# breakout.net
KiCad netlist of a schematic drawn in Altium Designer
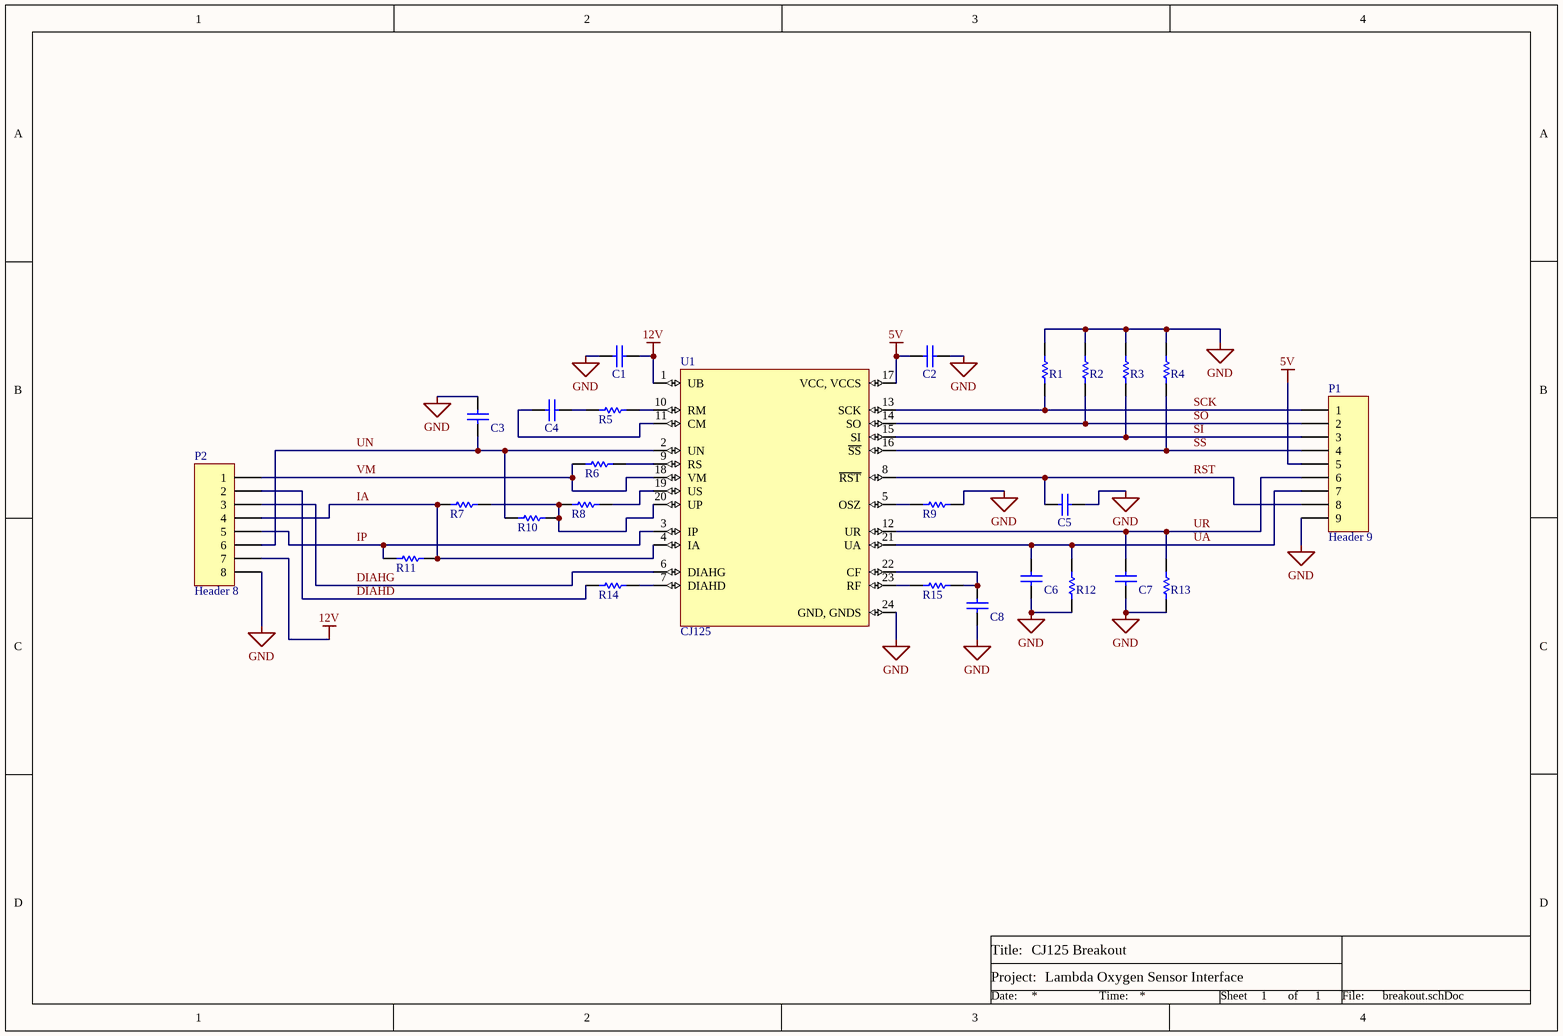
[diagram p0: breakout.schDoc]

(export (version "E")
  (design (tool "Eeschema 10.0.6"))
  (components
    (comp (ref "C1")
      (value "Generic 0805 Capacitor")
      (footprint "0805")
      (libsource (lib "symbol_library") (part "C_0805"))
    )
    (comp (ref "C2")
      (value "Generic 0805 Capacitor")
      (footprint "0805")
      (libsource (lib "symbol_library") (part "C_0805"))
    )
    (comp (ref "C3")
      (value "Generic 0805 Capacitor")
      (footprint "0805")
      (libsource (lib "symbol_library") (part "C_0805"))
    )
    (comp (ref "C4")
      (value "Generic 0805 Capacitor")
      (footprint "0805")
      (libsource (lib "symbol_library") (part "C_0805"))
    )
    (comp (ref "C5")
      (value "Generic 0805 Capacitor")
      (footprint "0805")
      (libsource (lib "symbol_library") (part "C_0805"))
    )
    (comp (ref "C6")
      (value "Generic 0805 Capacitor")
      (footprint "0805")
      (libsource (lib "symbol_library") (part "C_0805"))
    )
    (comp (ref "C7")
      (value "Generic 0805 Capacitor")
      (footprint "0805")
      (libsource (lib "symbol_library") (part "C_0805"))
    )
    (comp (ref "C8")
      (value "Generic 0805 Capacitor")
      (footprint "0805")
      (libsource (lib "symbol_library") (part "C_0805"))
    )
    (comp (ref "P1")
      (value "Header 9")
      (footprint "HDR1X9")
      (description "Header, 9-Pin")
      (fields (field (name "PUBLISHER") "Altium Limited"))
      (libsource (lib "Miscellaneous Connectors") (part "Header 9"))
    )
    (comp (ref "P2")
      (value "Header 8")
      (footprint "HDR1X8")
      (description "Header, 8-Pin")
      (fields (field (name "PUBLISHER") "Altium Limited"))
      (libsource (lib "Miscellaneous Connectors") (part "Header 8"))
    )
    (comp (ref "R1")
      (value "Generic 0603 Resistor")
      (footprint "0603")
      (libsource (lib "symbol_library") (part "R_0603"))
    )
    (comp (ref "R2")
      (value "Generic 0603 Resistor")
      (footprint "0603")
      (libsource (lib "symbol_library") (part "R_0603"))
    )
    (comp (ref "R3")
      (value "Generic 0603 Resistor")
      (footprint "0603")
      (libsource (lib "symbol_library") (part "R_0603"))
    )
    (comp (ref "R4")
      (value "Generic 0603 Resistor")
      (footprint "0603")
      (libsource (lib "symbol_library") (part "R_0603"))
    )
    (comp (ref "R5")
      (value "Generic 0603 Resistor")
      (footprint "0603")
      (libsource (lib "symbol_library") (part "R_0603"))
    )
    (comp (ref "R6")
      (value "Generic 0603 Resistor")
      (footprint "0603")
      (libsource (lib "symbol_library") (part "R_0603"))
    )
    (comp (ref "R7")
      (value "Generic 0603 Resistor")
      (footprint "0603")
      (libsource (lib "symbol_library") (part "R_0603"))
    )
    (comp (ref "R8")
      (value "Generic 0603 Resistor")
      (footprint "0603")
      (libsource (lib "symbol_library") (part "R_0603"))
    )
    (comp (ref "R9")
      (value "Generic 0603 Resistor")
      (footprint "0603")
      (libsource (lib "symbol_library") (part "R_0603"))
    )
    (comp (ref "R10")
      (value "Generic 0603 Resistor")
      (footprint "0603")
      (libsource (lib "symbol_library") (part "R_0603"))
    )
    (comp (ref "R11")
      (value "Generic 0603 Resistor")
      (footprint "0603")
      (libsource (lib "symbol_library") (part "R_0603"))
    )
    (comp (ref "R12")
      (value "Generic 0603 Resistor")
      (footprint "0603")
      (libsource (lib "symbol_library") (part "R_0603"))
    )
    (comp (ref "R13")
      (value "Generic 0603 Resistor")
      (footprint "0603")
      (libsource (lib "symbol_library") (part "R_0603"))
    )
    (comp (ref "R14")
      (value "Generic 0603 Resistor")
      (footprint "0603")
      (libsource (lib "symbol_library") (part "R_0603"))
    )
    (comp (ref "R15")
      (value "Generic 0603 Resistor")
      (footprint "0603")
      (libsource (lib "symbol_library") (part "R_0603"))
    )
    (comp (ref "U1")
      (value "CJ125")
      (footprint "SOIC-24")
      (description "5V 2Mbaud SMT Lambda Probe Interface IC - SOIC-24")
      (libsource (lib "symbol_library") (part "CJ125"))
    )
  )
  (nets
    (net (code "1") (name "/DIAHD") (class "Default")
      (node (ref "P2") (pin "2") (pinfunction "2_2") (pintype "passive"))
      (node (ref "R14") (pin "1") (pinfunction "1_1") (pintype "passive"))
    )
    (net (code "2") (name "/DIAHG") (class "Default")
      (node (ref "P2") (pin "3") (pinfunction "3_3") (pintype "passive"))
      (node (ref "U1") (pin "6") (pinfunction "DIAHG_6") (pintype "bidirectional"))
    )
    (net (code "3") (name "/IA") (class "Default")
      (node (ref "P2") (pin "4") (pinfunction "4_4") (pintype "passive"))
      (node (ref "R11") (pin "2") (pinfunction "2_2") (pintype "passive"))
      (node (ref "R7") (pin "1") (pinfunction "1_1") (pintype "passive"))
      (node (ref "U1") (pin "4") (pinfunction "IA_4") (pintype "bidirectional"))
    )
    (net (code "4") (name "/IP") (class "Default")
      (node (ref "P2") (pin "5") (pinfunction "5_5") (pintype "passive"))
      (node (ref "R11") (pin "1") (pinfunction "1_1") (pintype "passive"))
      (node (ref "U1") (pin "3") (pinfunction "IP_3") (pintype "bidirectional"))
    )
    (net (code "5") (name "/RST") (class "Default")
      (node (ref "C5") (pin "1") (pinfunction "1_1") (pintype "passive"))
      (node (ref "P1") (pin "8") (pinfunction "8_8") (pintype "passive"))
      (node (ref "U1") (pin "8") (pinfunction "~{RST}_8") (pintype "bidirectional"))
    )
    (net (code "6") (name "/SCK") (class "Default")
      (node (ref "P1") (pin "1") (pinfunction "1_1") (pintype "passive"))
      (node (ref "R1") (pin "1") (pinfunction "1_1") (pintype "passive"))
      (node (ref "U1") (pin "13") (pinfunction "SCK_13") (pintype "bidirectional"))
    )
    (net (code "7") (name "/SI") (class "Default")
      (node (ref "P1") (pin "3") (pinfunction "3_3") (pintype "passive"))
      (node (ref "R3") (pin "1") (pinfunction "1_1") (pintype "passive"))
      (node (ref "U1") (pin "15") (pinfunction "SI_15") (pintype "bidirectional"))
    )
    (net (code "8") (name "/SO") (class "Default")
      (node (ref "P1") (pin "2") (pinfunction "2_2") (pintype "passive"))
      (node (ref "R2") (pin "1") (pinfunction "1_1") (pintype "passive"))
      (node (ref "U1") (pin "14") (pinfunction "SO_14") (pintype "bidirectional"))
    )
    (net (code "9") (name "/SS") (class "Default")
      (node (ref "P1") (pin "4") (pinfunction "4_4") (pintype "passive"))
      (node (ref "R4") (pin "1") (pinfunction "1_1") (pintype "passive"))
      (node (ref "U1") (pin "16") (pinfunction "~{SS}_16") (pintype "bidirectional"))
    )
    (net (code "10") (name "/UA") (class "Default")
      (node (ref "C6") (pin "2") (pinfunction "2_2") (pintype "passive"))
      (node (ref "P1") (pin "7") (pinfunction "7_7") (pintype "passive"))
      (node (ref "R12") (pin "2") (pinfunction "2_2") (pintype "passive"))
      (node (ref "U1") (pin "21") (pinfunction "UA_21") (pintype "bidirectional"))
    )
    (net (code "11") (name "/UN") (class "Default")
      (node (ref "C3") (pin "1") (pinfunction "1_1") (pintype "passive"))
      (node (ref "P2") (pin "6") (pinfunction "6_6") (pintype "passive"))
      (node (ref "R10") (pin "1") (pinfunction "1_1") (pintype "passive"))
      (node (ref "U1") (pin "2") (pinfunction "UN_2") (pintype "bidirectional"))
    )
    (net (code "12") (name "/UR") (class "Default")
      (node (ref "C7") (pin "2") (pinfunction "2_2") (pintype "passive"))
      (node (ref "P1") (pin "6") (pinfunction "6_6") (pintype "passive"))
      (node (ref "R13") (pin "2") (pinfunction "2_2") (pintype "passive"))
      (node (ref "U1") (pin "12") (pinfunction "UR_12") (pintype "bidirectional"))
    )
    (net (code "13") (name "/VM") (class "Default")
      (node (ref "P2") (pin "1") (pinfunction "1_1") (pintype "passive"))
      (node (ref "R6") (pin "1") (pinfunction "1_1") (pintype "passive"))
      (node (ref "U1") (pin "18") (pinfunction "VM_18") (pintype "bidirectional"))
    )
    (net (code "14") (name "5V") (class "Default")
      (node (ref "C2") (pin "1") (pinfunction "1_1") (pintype "passive"))
      (node (ref "P1") (pin "5") (pinfunction "5_5") (pintype "passive"))
      (node (ref "U1") (pin "17") (pinfunction "VCC,_VCCS_17") (pintype "bidirectional"))
    )
    (net (code "15") (name "12V") (class "Default")
      (node (ref "C1") (pin "2") (pinfunction "2_2") (pintype "passive"))
      (node (ref "P2") (pin "7") (pinfunction "7_7") (pintype "passive"))
      (node (ref "U1") (pin "1") (pinfunction "UB_1") (pintype "bidirectional"))
    )
    (net (code "16") (name "GND") (class "Default")
      (node (ref "C1") (pin "1") (pinfunction "1_1") (pintype "passive"))
      (node (ref "C2") (pin "2") (pinfunction "2_2") (pintype "passive"))
      (node (ref "C3") (pin "2") (pinfunction "2_2") (pintype "passive"))
      (node (ref "C5") (pin "2") (pinfunction "2_2") (pintype "passive"))
      (node (ref "C6") (pin "1") (pinfunction "1_1") (pintype "passive"))
      (node (ref "C7") (pin "1") (pinfunction "1_1") (pintype "passive"))
      (node (ref "C8") (pin "1") (pinfunction "1_1") (pintype "passive"))
      (node (ref "P1") (pin "9") (pinfunction "9_9") (pintype "passive"))
      (node (ref "P2") (pin "8") (pinfunction "8_8") (pintype "passive"))
      (node (ref "R1") (pin "2") (pinfunction "2_2") (pintype "passive"))
      (node (ref "R12") (pin "1") (pinfunction "1_1") (pintype "passive"))
      (node (ref "R13") (pin "1") (pinfunction "1_1") (pintype "passive"))
      (node (ref "R2") (pin "2") (pinfunction "2_2") (pintype "passive"))
      (node (ref "R3") (pin "2") (pinfunction "2_2") (pintype "passive"))
      (node (ref "R4") (pin "2") (pinfunction "2_2") (pintype "passive"))
      (node (ref "R9") (pin "2") (pinfunction "2_2") (pintype "passive"))
      (node (ref "U1") (pin "24") (pinfunction "GND,_GNDS_24") (pintype "bidirectional"))
    )
    (net (code "17") (name "Net-(C4-Pad2)") (class "Default")
      (node (ref "C4") (pin "2") (pinfunction "2_2") (pintype "passive"))
      (node (ref "R5") (pin "1") (pinfunction "1_1") (pintype "passive"))
    )
    (net (code "18") (name "Net-(U1-CF)") (class "Default")
      (node (ref "C8") (pin "2") (pinfunction "2_2") (pintype "passive"))
      (node (ref "R15") (pin "2") (pinfunction "2_2") (pintype "passive"))
      (node (ref "U1") (pin "22") (pinfunction "CF_22") (pintype "bidirectional"))
    )
    (net (code "19") (name "Net-(U1-CM)") (class "Default")
      (node (ref "C4") (pin "1") (pinfunction "1_1") (pintype "passive"))
      (node (ref "U1") (pin "11") (pinfunction "CM_11") (pintype "bidirectional"))
    )
    (net (code "20") (name "Net-(U1-DIAHD)") (class "Default")
      (node (ref "R14") (pin "2") (pinfunction "2_2") (pintype "passive"))
      (node (ref "U1") (pin "7") (pinfunction "DIAHD_7") (pintype "bidirectional"))
    )
    (net (code "21") (name "Net-(U1-OSZ)") (class "Default")
      (node (ref "R9") (pin "1") (pinfunction "1_1") (pintype "passive"))
      (node (ref "U1") (pin "5") (pinfunction "OSZ_5") (pintype "bidirectional"))
    )
    (net (code "22") (name "Net-(U1-RF)") (class "Default")
      (node (ref "R15") (pin "1") (pinfunction "1_1") (pintype "passive"))
      (node (ref "U1") (pin "23") (pinfunction "RF_23") (pintype "bidirectional"))
    )
    (net (code "23") (name "Net-(U1-RM)") (class "Default")
      (node (ref "R5") (pin "2") (pinfunction "2_2") (pintype "passive"))
      (node (ref "U1") (pin "10") (pinfunction "RM_10") (pintype "bidirectional"))
    )
    (net (code "24") (name "Net-(U1-RS)") (class "Default")
      (node (ref "R6") (pin "2") (pinfunction "2_2") (pintype "passive"))
      (node (ref "U1") (pin "9") (pinfunction "RS_9") (pintype "bidirectional"))
    )
    (net (code "25") (name "Net-(U1-UP)") (class "Default")
      (node (ref "R10") (pin "2") (pinfunction "2_2") (pintype "passive"))
      (node (ref "R7") (pin "2") (pinfunction "2_2") (pintype "passive"))
      (node (ref "R8") (pin "1") (pinfunction "1_1") (pintype "passive"))
      (node (ref "U1") (pin "20") (pinfunction "UP_20") (pintype "bidirectional"))
    )
    (net (code "26") (name "Net-(U1-US)") (class "Default")
      (node (ref "R8") (pin "2") (pinfunction "2_2") (pintype "passive"))
      (node (ref "U1") (pin "19") (pinfunction "US_19") (pintype "bidirectional"))
    )
  )
)
